# tach_key.net
KiCad netlist of a schematic drawn in Altium Designer
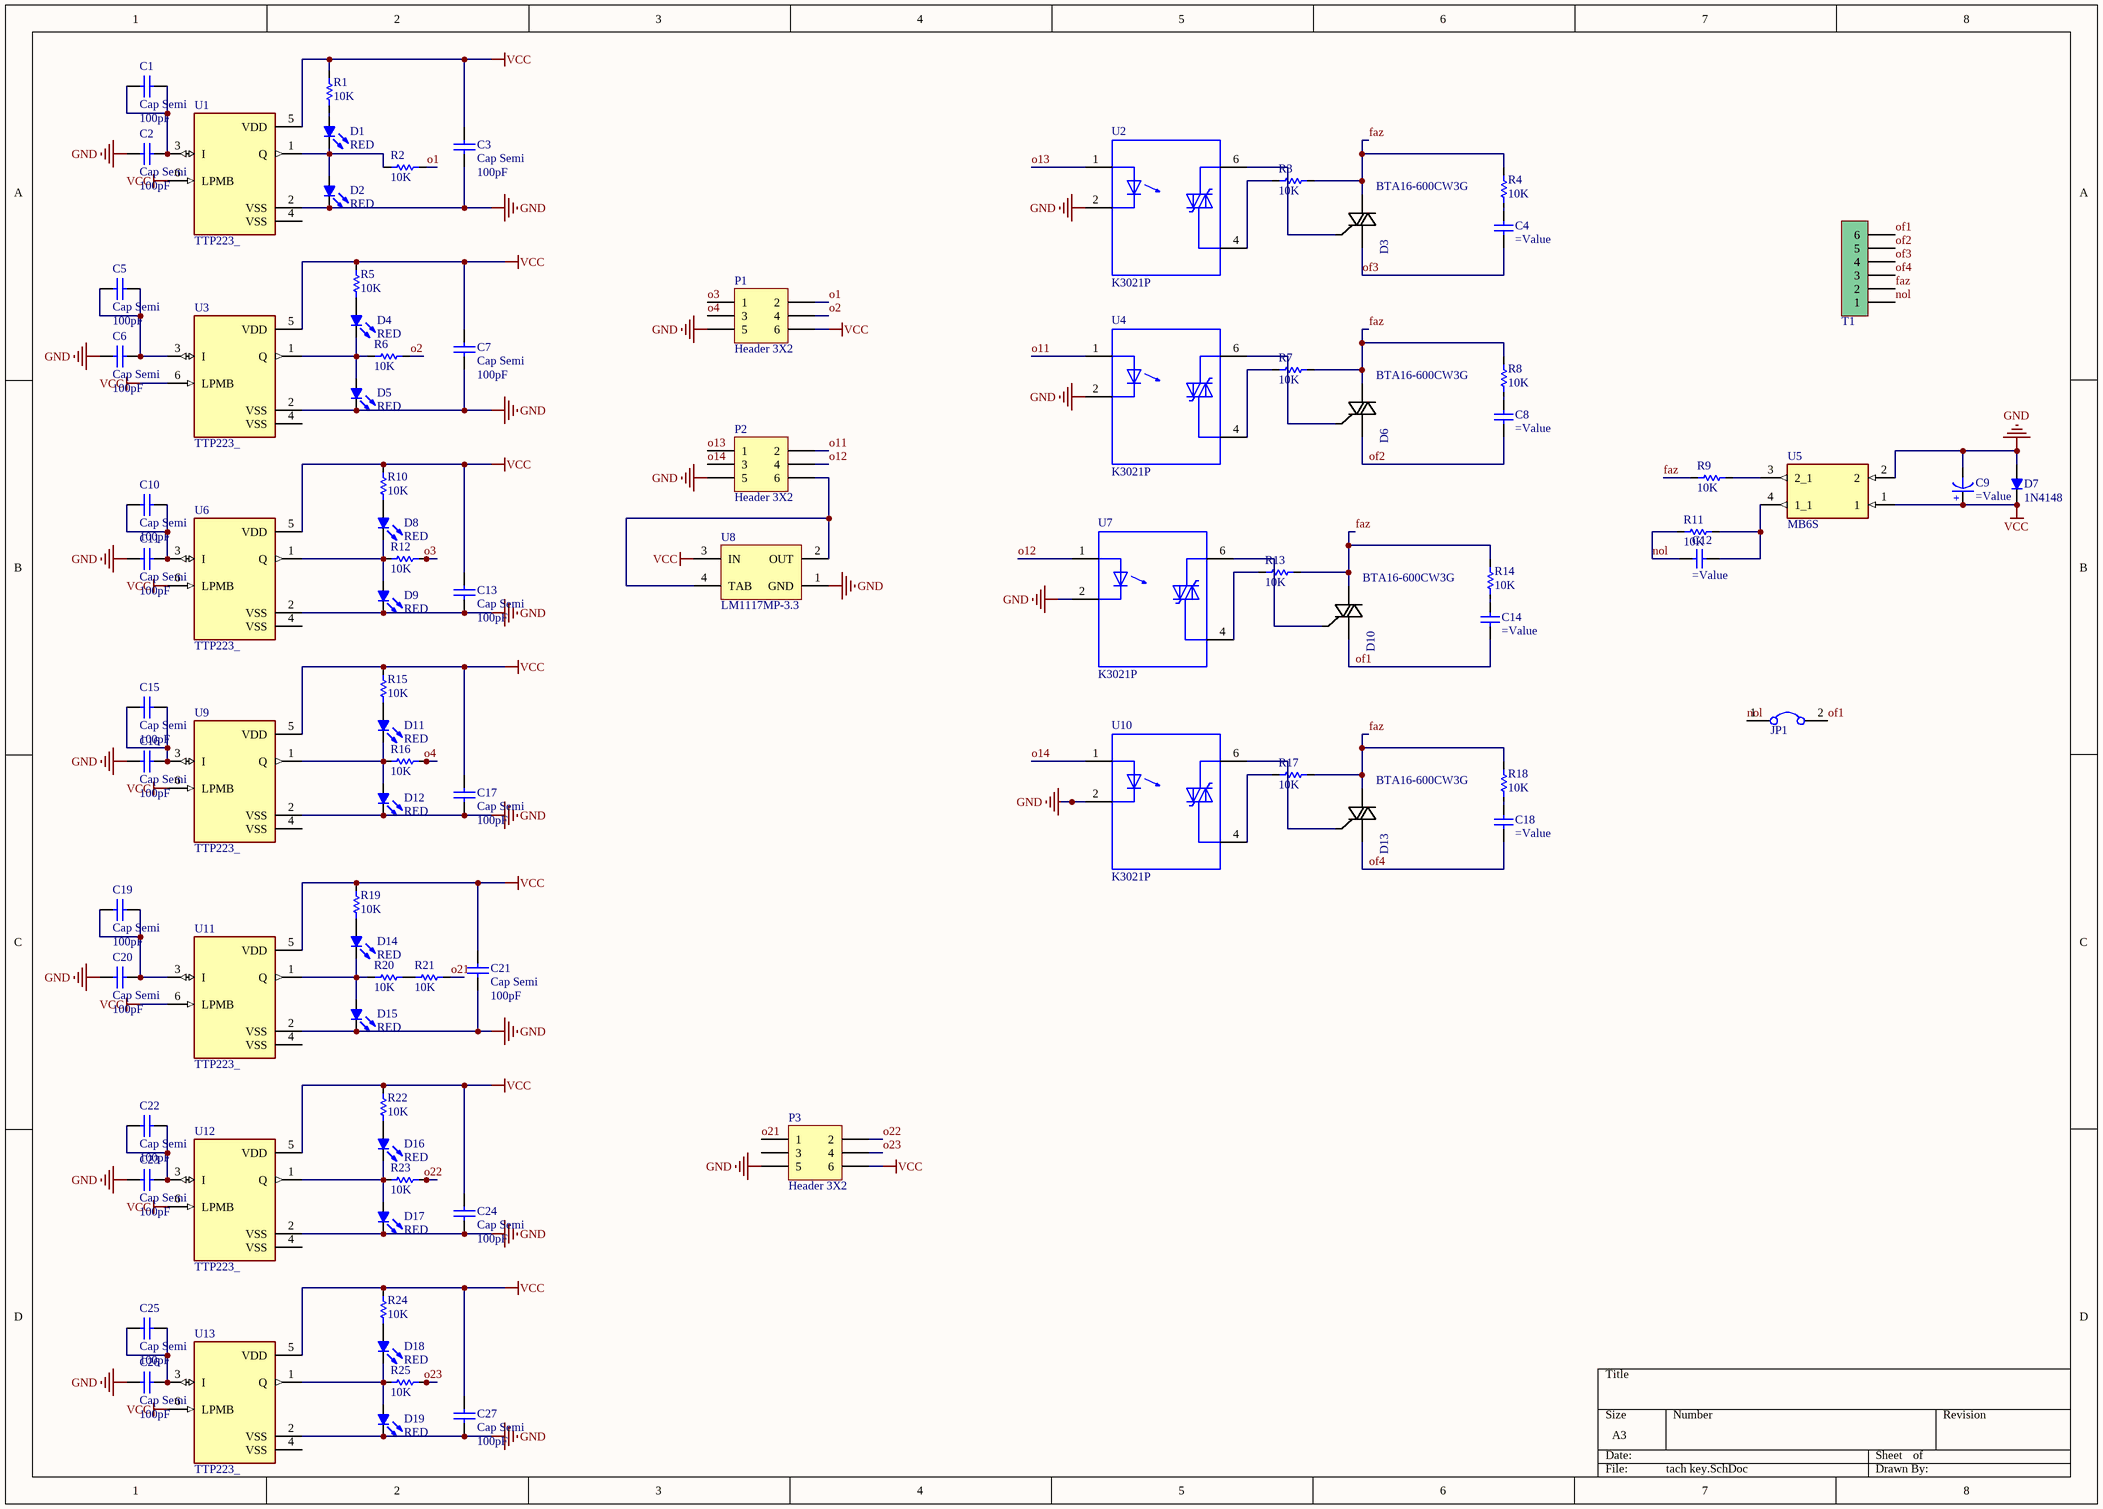
[diagram p0: tach key.SchDoc]

(export (version "E")
  (design (tool "Eeschema 10.0.6"))
  (components
    (comp (ref "C1")
      (value "Cap Semi")
      (footprint "C1206")
      (description "Capacitor (Semiconductor SIM Model)")
      (fields (field (name "ALTIUM_VALUE") "100pF") (field (name "PUBLISHER") "Altium Limited"))
      (libsource (lib "Miscellaneous Devices") (part "Cap Semi"))
    )
    (comp (ref "C2")
      (value "Cap Semi")
      (footprint "C1206")
      (description "Capacitor (Semiconductor SIM Model)")
      (fields (field (name "ALTIUM_VALUE") "100pF") (field (name "PUBLISHER") "Altium Limited"))
      (libsource (lib "Miscellaneous Devices") (part "Cap Semi"))
    )
    (comp (ref "C3")
      (value "Cap Semi")
      (footprint "C1206")
      (description "Capacitor (Semiconductor SIM Model)")
      (fields (field (name "ALTIUM_VALUE") "100pF") (field (name "PUBLISHER") "Altium Limited"))
      (libsource (lib "Miscellaneous Devices") (part "Cap Semi"))
    )
    (comp (ref "C4")
      (value "~")
      (footprint "CAP-30")
      (description "Capacitor")
      (libsource (lib "AltiumLib1") (part "Capacitor"))
    )
    (comp (ref "C5")
      (value "Cap Semi")
      (footprint "C1206")
      (description "Capacitor (Semiconductor SIM Model)")
      (fields (field (name "ALTIUM_VALUE") "100pF") (field (name "PUBLISHER") "Altium Limited"))
      (libsource (lib "Miscellaneous Devices") (part "Cap Semi"))
    )
    (comp (ref "C6")
      (value "Cap Semi")
      (footprint "C1206")
      (description "Capacitor (Semiconductor SIM Model)")
      (fields (field (name "ALTIUM_VALUE") "100pF") (field (name "PUBLISHER") "Altium Limited"))
      (libsource (lib "Miscellaneous Devices") (part "Cap Semi"))
    )
    (comp (ref "C7")
      (value "Cap Semi")
      (footprint "C1206")
      (description "Capacitor (Semiconductor SIM Model)")
      (fields (field (name "ALTIUM_VALUE") "100pF") (field (name "PUBLISHER") "Altium Limited"))
      (libsource (lib "Miscellaneous Devices") (part "Cap Semi"))
    )
    (comp (ref "C8")
      (value "~")
      (footprint "CAP-30")
      (description "Capacitor")
      (libsource (lib "AltiumLib1") (part "Capacitor"))
    )
    (comp (ref "C9")
      (value "~")
      (footprint "ELEC-CAP-RAD10-20")
      (description "Electrolytic Capacitor")
      (libsource (lib "AltiumLib1") (part "Capacitor Electrolytic"))
    )
    (comp (ref "C10")
      (value "Cap Semi")
      (footprint "C1206")
      (description "Capacitor (Semiconductor SIM Model)")
      (fields (field (name "ALTIUM_VALUE") "100pF") (field (name "PUBLISHER") "Altium Limited"))
      (libsource (lib "Miscellaneous Devices") (part "Cap Semi"))
    )
    (comp (ref "C11")
      (value "Cap Semi")
      (footprint "C1206")
      (description "Capacitor (Semiconductor SIM Model)")
      (fields (field (name "ALTIUM_VALUE") "100pF") (field (name "PUBLISHER") "Altium Limited"))
      (libsource (lib "Miscellaneous Devices") (part "Cap Semi"))
    )
    (comp (ref "C12")
      (value "~")
      (footprint "CAP-30")
      (description "Capacitor")
      (libsource (lib "AltiumLib1") (part "Capacitor"))
    )
    (comp (ref "C13")
      (value "Cap Semi")
      (footprint "C0805")
      (description "Capacitor (Semiconductor SIM Model)")
      (fields (field (name "ALTIUM_VALUE") "100pF") (field (name "PUBLISHER") "Altium Limited"))
      (libsource (lib "Miscellaneous Devices") (part "Cap Semi"))
    )
    (comp (ref "C14")
      (value "~")
      (footprint "CAP-30")
      (description "Capacitor")
      (libsource (lib "AltiumLib1") (part "Capacitor"))
    )
    (comp (ref "C15")
      (value "Cap Semi")
      (footprint "C1206")
      (description "Capacitor (Semiconductor SIM Model)")
      (fields (field (name "ALTIUM_VALUE") "100pF") (field (name "PUBLISHER") "Altium Limited"))
      (libsource (lib "Miscellaneous Devices") (part "Cap Semi"))
    )
    (comp (ref "C16")
      (value "Cap Semi")
      (footprint "C1206")
      (description "Capacitor (Semiconductor SIM Model)")
      (fields (field (name "ALTIUM_VALUE") "100pF") (field (name "PUBLISHER") "Altium Limited"))
      (libsource (lib "Miscellaneous Devices") (part "Cap Semi"))
    )
    (comp (ref "C17")
      (value "Cap Semi")
      (footprint "C0805")
      (description "Capacitor (Semiconductor SIM Model)")
      (fields (field (name "ALTIUM_VALUE") "100pF") (field (name "PUBLISHER") "Altium Limited"))
      (libsource (lib "Miscellaneous Devices") (part "Cap Semi"))
    )
    (comp (ref "C18")
      (value "~")
      (footprint "CAP-30")
      (description "Capacitor")
      (libsource (lib "AltiumLib1") (part "Capacitor"))
    )
    (comp (ref "C19")
      (value "Cap Semi")
      (footprint "C1206")
      (description "Capacitor (Semiconductor SIM Model)")
      (fields (field (name "ALTIUM_VALUE") "100pF") (field (name "PUBLISHER") "Altium Limited"))
      (libsource (lib "Miscellaneous Devices") (part "Cap Semi"))
    )
    (comp (ref "C20")
      (value "Cap Semi")
      (footprint "C1206")
      (description "Capacitor (Semiconductor SIM Model)")
      (fields (field (name "ALTIUM_VALUE") "100pF") (field (name "PUBLISHER") "Altium Limited"))
      (libsource (lib "Miscellaneous Devices") (part "Cap Semi"))
    )
    (comp (ref "C21")
      (value "Cap Semi")
      (footprint "C1206")
      (description "Capacitor (Semiconductor SIM Model)")
      (fields (field (name "ALTIUM_VALUE") "100pF") (field (name "PUBLISHER") "Altium Limited"))
      (libsource (lib "Miscellaneous Devices") (part "Cap Semi"))
    )
    (comp (ref "C22")
      (value "Cap Semi")
      (footprint "C1206")
      (description "Capacitor (Semiconductor SIM Model)")
      (fields (field (name "ALTIUM_VALUE") "100pF") (field (name "PUBLISHER") "Altium Limited"))
      (libsource (lib "Miscellaneous Devices") (part "Cap Semi"))
    )
    (comp (ref "C23")
      (value "Cap Semi")
      (footprint "C1206")
      (description "Capacitor (Semiconductor SIM Model)")
      (fields (field (name "ALTIUM_VALUE") "100pF") (field (name "PUBLISHER") "Altium Limited"))
      (libsource (lib "Miscellaneous Devices") (part "Cap Semi"))
    )
    (comp (ref "C24")
      (value "Cap Semi")
      (footprint "C0805")
      (description "Capacitor (Semiconductor SIM Model)")
      (fields (field (name "ALTIUM_VALUE") "100pF") (field (name "PUBLISHER") "Altium Limited"))
      (libsource (lib "Miscellaneous Devices") (part "Cap Semi"))
    )
    (comp (ref "C25")
      (value "Cap Semi")
      (footprint "C1206")
      (description "Capacitor (Semiconductor SIM Model)")
      (fields (field (name "ALTIUM_VALUE") "100pF") (field (name "PUBLISHER") "Altium Limited"))
      (libsource (lib "Miscellaneous Devices") (part "Cap Semi"))
    )
    (comp (ref "C26")
      (value "Cap Semi")
      (footprint "C1206")
      (description "Capacitor (Semiconductor SIM Model)")
      (fields (field (name "ALTIUM_VALUE") "100pF") (field (name "PUBLISHER") "Altium Limited"))
      (libsource (lib "Miscellaneous Devices") (part "Cap Semi"))
    )
    (comp (ref "C27")
      (value "Cap Semi")
      (footprint "C0805")
      (description "Capacitor (Semiconductor SIM Model)")
      (fields (field (name "ALTIUM_VALUE") "100pF") (field (name "PUBLISHER") "Altium Limited"))
      (libsource (lib "Miscellaneous Devices") (part "Cap Semi"))
    )
    (comp (ref "D1")
      (value "MODEL")
      (footprint "RES 0805 (2012X06L)")
      (description "Typical LED")
      (fields (field (name "COLOR") "RED"))
      (libsource (lib "AltiumLib1") (part "LED 5mm"))
    )
    (comp (ref "D2")
      (value "MODEL")
      (footprint "RES 0805 (2012X06L)")
      (description "Typical LED")
      (fields (field (name "COLOR") "RED"))
      (libsource (lib "AltiumLib1") (part "LED 5mm"))
    )
    (comp (ref "D3")
      (value "BTA16-600CW3G")
      (footprint "*TO254P1028X482X1968-3")
      (description "TRIAC Standard 600V 16A Through Hole TO-220AB")
      (fields (field (name "MF") "Littelfuse Inc."))
      (libsource (lib "BTA16-600CW3G") (part "BTA16-600CW3G"))
    )
    (comp (ref "D4")
      (value "MODEL")
      (footprint "RES 0805 (2012X06L)")
      (description "Typical LED")
      (fields (field (name "COLOR") "RED"))
      (libsource (lib "AltiumLib1") (part "LED 5mm"))
    )
    (comp (ref "D5")
      (value "MODEL")
      (footprint "RES 0805 (2012X06L)")
      (description "Typical LED")
      (fields (field (name "COLOR") "RED"))
      (libsource (lib "AltiumLib1") (part "LED 5mm"))
    )
    (comp (ref "D6")
      (value "BTA16-600CW3G")
      (footprint "*TO254P1028X482X1968-3")
      (description "TRIAC Standard 600V 16A Through Hole TO-220AB")
      (fields (field (name "MF") "Littelfuse Inc."))
      (libsource (lib "BTA16-600CW3G") (part "BTA16-600CW3G"))
    )
    (comp (ref "D7")
      (value "MODEL")
      (footprint "DO-35-STAND")
      (description "Diode")
      (fields (field (name "MODEL") "1N4148"))
      (libsource (lib "AltiumLib1") (part "Diode"))
    )
    (comp (ref "D8")
      (value "MODEL")
      (footprint "RES 0805 (2012X06L)")
      (description "Typical LED")
      (fields (field (name "COLOR") "RED"))
      (libsource (lib "AltiumLib1") (part "LED 5mm"))
    )
    (comp (ref "D9")
      (value "MODEL")
      (footprint "RES 0805 (2012X06L)")
      (description "Typical LED")
      (fields (field (name "COLOR") "RED"))
      (libsource (lib "AltiumLib1") (part "LED 5mm"))
    )
    (comp (ref "D10")
      (value "BTA16-600CW3G")
      (footprint "*TO254P1028X482X1968-3")
      (description "TRIAC Standard 600V 16A Through Hole TO-220AB")
      (fields (field (name "MF") "Littelfuse Inc."))
      (libsource (lib "BTA16-600CW3G") (part "BTA16-600CW3G"))
    )
    (comp (ref "D11")
      (value "MODEL")
      (footprint "RES 0805 (2012X06L)")
      (description "Typical LED")
      (fields (field (name "COLOR") "RED"))
      (libsource (lib "AltiumLib1") (part "LED 5mm"))
    )
    (comp (ref "D12")
      (value "MODEL")
      (footprint "RES 0805 (2012X06L)")
      (description "Typical LED")
      (fields (field (name "COLOR") "RED"))
      (libsource (lib "AltiumLib1") (part "LED 5mm"))
    )
    (comp (ref "D13")
      (value "BTA16-600CW3G")
      (footprint "*TO254P1028X482X1968-3")
      (description "TRIAC Standard 600V 16A Through Hole TO-220AB")
      (fields (field (name "MF") "Littelfuse Inc."))
      (libsource (lib "BTA16-600CW3G") (part "BTA16-600CW3G"))
    )
    (comp (ref "D14")
      (value "MODEL")
      (footprint "RES 0805 (2012X06L)")
      (description "Typical LED")
      (fields (field (name "COLOR") "RED"))
      (libsource (lib "AltiumLib1") (part "LED 5mm"))
    )
    (comp (ref "D15")
      (value "MODEL")
      (footprint "RES 0805 (2012X06L)")
      (description "Typical LED")
      (fields (field (name "COLOR") "RED"))
      (libsource (lib "AltiumLib1") (part "LED 5mm"))
    )
    (comp (ref "D16")
      (value "MODEL")
      (footprint "RES 0805 (2012X06L)")
      (description "Typical LED")
      (fields (field (name "COLOR") "RED"))
      (libsource (lib "AltiumLib1") (part "LED 5mm"))
    )
    (comp (ref "D17")
      (value "MODEL")
      (footprint "RES 0805 (2012X06L)")
      (description "Typical LED")
      (fields (field (name "COLOR") "RED"))
      (libsource (lib "AltiumLib1") (part "LED 5mm"))
    )
    (comp (ref "D18")
      (value "MODEL")
      (footprint "RES 0805 (2012X06L)")
      (description "Typical LED")
      (fields (field (name "COLOR") "RED"))
      (libsource (lib "AltiumLib1") (part "LED 5mm"))
    )
    (comp (ref "D19")
      (value "MODEL")
      (footprint "RES 0805 (2012X06L)")
      (description "Typical LED")
      (fields (field (name "COLOR") "RED"))
      (libsource (lib "AltiumLib1") (part "LED 5mm"))
    )
    (comp (ref "JP1")
      (value "Jumper")
      (footprint "Header 2X1")
      (libsource (lib "AltiumLib1") (part "Jumper"))
    )
    (comp (ref "P1")
      (value "Header 3X2")
      (footprint "HDR2X3")
      (description "Header, 3-Pin, Dual row")
      (fields (field (name "PUBLISHER") "Altium Limited"))
      (libsource (lib "Miscellaneous Connectors") (part "Header 3X2"))
    )
    (comp (ref "P2")
      (value "Header 3X2")
      (footprint "MHDR2X3")
      (description "Header, 3-Pin, Dual row")
      (fields (field (name "PUBLISHER") "Altium Limited"))
      (libsource (lib "Miscellaneous Connectors") (part "Header 3X2"))
    )
    (comp (ref "P3")
      (value "Header 3X2")
      (footprint "MHDR2X3")
      (description "Header, 3-Pin, Dual row")
      (fields (field (name "PUBLISHER") "Altium Limited"))
      (libsource (lib "Miscellaneous Connectors") (part "Header 3X2"))
    )
    (comp (ref "R1")
      (value "10K")
      (footprint "RES 1206 (3216X08L)")
      (description "Resistor")
      (fields (field (name "TOLERANCE") "5%") (field (name "POWER") "1/4 W"))
      (libsource (lib "AltiumLib1") (part "Resistor"))
    )
    (comp (ref "R2")
      (value "10K")
      (footprint "RES 1206 (3216X08L)")
      (description "Resistor")
      (fields (field (name "TOLERANCE") "5%") (field (name "POWER") "1/4 W"))
      (libsource (lib "AltiumLib1") (part "Resistor"))
    )
    (comp (ref "R3")
      (value "10K")
      (footprint "RES 1206 (3216X08L)")
      (description "Resistor")
      (fields (field (name "TOLERANCE") "5%") (field (name "POWER") "1/4 W"))
      (libsource (lib "AltiumLib1") (part "Resistor"))
    )
    (comp (ref "R4")
      (value "10K")
      (footprint "RES 1206 (3216X08L)")
      (description "Resistor")
      (fields (field (name "TOLERANCE") "5%") (field (name "POWER") "1/4 W"))
      (libsource (lib "AltiumLib1") (part "Resistor"))
    )
    (comp (ref "R5")
      (value "10K")
      (footprint "RES 1206 (3216X08L)")
      (description "Resistor")
      (fields (field (name "TOLERANCE") "5%") (field (name "POWER") "1/4 W"))
      (libsource (lib "AltiumLib1") (part "Resistor"))
    )
    (comp (ref "R6")
      (value "10K")
      (footprint "RES 1206 (3216X08L)")
      (description "Resistor")
      (fields (field (name "TOLERANCE") "5%") (field (name "POWER") "1/4 W"))
      (libsource (lib "AltiumLib1") (part "Resistor"))
    )
    (comp (ref "R7")
      (value "10K")
      (footprint "RES 1206 (3216X08L)")
      (description "Resistor")
      (fields (field (name "TOLERANCE") "5%") (field (name "POWER") "1/4 W"))
      (libsource (lib "AltiumLib1") (part "Resistor"))
    )
    (comp (ref "R8")
      (value "10K")
      (footprint "RES 1206 (3216X08L)")
      (description "Resistor")
      (fields (field (name "TOLERANCE") "5%") (field (name "POWER") "1/4 W"))
      (libsource (lib "AltiumLib1") (part "Resistor"))
    )
    (comp (ref "R9")
      (value "10K")
      (footprint "Res-(2/1)")
      (description "Resistor")
      (fields (field (name "TOLERANCE") "5%") (field (name "POWER") "1/4 W"))
      (libsource (lib "AltiumLib1") (part "Resistor"))
    )
    (comp (ref "R10")
      (value "10K")
      (footprint "RES 1206 (3216X08L)")
      (description "Resistor")
      (fields (field (name "TOLERANCE") "5%") (field (name "POWER") "1/4 W"))
      (libsource (lib "AltiumLib1") (part "Resistor"))
    )
    (comp (ref "R11")
      (value "10K")
      (footprint "Res-(1/4)")
      (description "Resistor")
      (fields (field (name "TOLERANCE") "5%") (field (name "POWER") "1/4 W"))
      (libsource (lib "AltiumLib1") (part "Resistor"))
    )
    (comp (ref "R12")
      (value "10K")
      (footprint "RES 1206 (3216X08L)")
      (description "Resistor")
      (fields (field (name "TOLERANCE") "5%") (field (name "POWER") "1/4 W"))
      (libsource (lib "AltiumLib1") (part "Resistor"))
    )
    (comp (ref "R13")
      (value "10K")
      (footprint "RES 1206 (3216X08L)")
      (description "Resistor")
      (fields (field (name "TOLERANCE") "5%") (field (name "POWER") "1/4 W"))
      (libsource (lib "AltiumLib1") (part "Resistor"))
    )
    (comp (ref "R14")
      (value "10K")
      (footprint "RES 1206 (3216X08L)")
      (description "Resistor")
      (fields (field (name "TOLERANCE") "5%") (field (name "POWER") "1/4 W"))
      (libsource (lib "AltiumLib1") (part "Resistor"))
    )
    (comp (ref "R15")
      (value "10K")
      (footprint "RES 1206 (3216X08L)")
      (description "Resistor")
      (fields (field (name "TOLERANCE") "5%") (field (name "POWER") "1/4 W"))
      (libsource (lib "AltiumLib1") (part "Resistor"))
    )
    (comp (ref "R16")
      (value "10K")
      (footprint "RES 1206 (3216X08L)")
      (description "Resistor")
      (fields (field (name "TOLERANCE") "5%") (field (name "POWER") "1/4 W"))
      (libsource (lib "AltiumLib1") (part "Resistor"))
    )
    (comp (ref "R17")
      (value "10K")
      (footprint "RES 1206 (3216X08L)")
      (description "Resistor")
      (fields (field (name "TOLERANCE") "5%") (field (name "POWER") "1/4 W"))
      (libsource (lib "AltiumLib1") (part "Resistor"))
    )
    (comp (ref "R18")
      (value "10K")
      (footprint "RES 1206 (3216X08L)")
      (description "Resistor")
      (fields (field (name "TOLERANCE") "5%") (field (name "POWER") "1/4 W"))
      (libsource (lib "AltiumLib1") (part "Resistor"))
    )
    (comp (ref "R19")
      (value "10K")
      (footprint "RES 1206 (3216X08L)")
      (description "Resistor")
      (fields (field (name "TOLERANCE") "5%") (field (name "POWER") "1/4 W"))
      (libsource (lib "AltiumLib1") (part "Resistor"))
    )
    (comp (ref "R20")
      (value "10K")
      (footprint "RES 1206 (3216X08L)")
      (description "Resistor")
      (fields (field (name "TOLERANCE") "5%") (field (name "POWER") "1/4 W"))
      (libsource (lib "AltiumLib1") (part "Resistor"))
    )
    (comp (ref "R21")
      (value "10K")
      (footprint "RES 1206 (3216X08L)")
      (description "Resistor")
      (fields (field (name "TOLERANCE") "5%") (field (name "POWER") "1/4 W"))
      (libsource (lib "AltiumLib1") (part "Resistor"))
    )
    (comp (ref "R22")
      (value "10K")
      (footprint "RES 1206 (3216X08L)")
      (description "Resistor")
      (fields (field (name "TOLERANCE") "5%") (field (name "POWER") "1/4 W"))
      (libsource (lib "AltiumLib1") (part "Resistor"))
    )
    (comp (ref "R23")
      (value "10K")
      (footprint "RES 1206 (3216X08L)")
      (description "Resistor")
      (fields (field (name "TOLERANCE") "5%") (field (name "POWER") "1/4 W"))
      (libsource (lib "AltiumLib1") (part "Resistor"))
    )
    (comp (ref "R24")
      (value "10K")
      (footprint "RES 1206 (3216X08L)")
      (description "Resistor")
      (fields (field (name "TOLERANCE") "5%") (field (name "POWER") "1/4 W"))
      (libsource (lib "AltiumLib1") (part "Resistor"))
    )
    (comp (ref "R25")
      (value "10K")
      (footprint "RES 1206 (3216X08L)")
      (description "Resistor")
      (fields (field (name "TOLERANCE") "5%") (field (name "POWER") "1/4 W"))
      (libsource (lib "AltiumLib1") (part "Resistor"))
    )
    (comp (ref "T1")
      (value "Phoenix terminal")
      (footprint "phoenix terminal 6")
      (description "Terminal 6 Pin")
      (fields (field (name "DESIGNER") "Seyed Mohsen Ghasemain") (field (name "E-MAIL") "picpars@gmail.com"))
      (libsource (lib "PicPars.com_usefully_Library") (part "Phoenix terminal 6"))
    )
    (comp (ref "U1")
      (value "TTP223_")
      (footprint "SOT95P285X126-6N")
      (fields (field (name "MP") "TTP223") (field (name "MF") "KOA Speer"))
      (libsource (lib "TTP223_") (part "TTP223_"))
    )
    (comp (ref "U2")
      (value "K3021P")
      (footprint "DIP762W50P254L730H410Q6")
      (description "Optoisolator Triac Output 5300Vrms 1 Channel 6-DIP")
      (fields (field (name "MF") "Vishay Semiconductor"))
      (libsource (lib "K3021P") (part "K3021P"))
    )
    (comp (ref "U3")
      (value "TTP223_")
      (footprint "SOT95P285X126-6N")
      (fields (field (name "MP") "TTP223") (field (name "MF") "KOA Speer"))
      (libsource (lib "TTP223_") (part "TTP223_"))
    )
    (comp (ref "U4")
      (value "K3021P")
      (footprint "DIP762W50P254L730H410Q6")
      (description "Optoisolator Triac Output 5300Vrms 1 Channel 6-DIP")
      (fields (field (name "MF") "Vishay Semiconductor"))
      (libsource (lib "K3021P") (part "K3021P"))
    )
    (comp (ref "U5")
      (value "MB6S")
      (footprint "SOIC245P670X270-4N")
      (description "Bridge Rectifier Single Phase Standard 600V Surface Mount 4-SOIC")
      (fields (field (name "MF") "ON Semiconductor") (field (name "DIGI-KEY_PART_NUMBER") "MB6SCT-ND"))
      (libsource (lib "MB6S") (part "MB6S"))
    )
    (comp (ref "U6")
      (value "TTP223_")
      (footprint "SOT95P285X126-6N")
      (fields (field (name "MP") "TTP223") (field (name "MF") "KOA Speer"))
      (libsource (lib "TTP223_") (part "TTP223_"))
    )
    (comp (ref "U7")
      (value "K3021P")
      (footprint "DIP762W50P254L730H410Q6")
      (description "Optoisolator Triac Output 5300Vrms 1 Channel 6-DIP")
      (fields (field (name "MF") "Vishay Semiconductor"))
      (libsource (lib "K3021P") (part "K3021P"))
    )
    (comp (ref "U8")
      (value "LM1117MP-3.3")
      (footprint "MP04A_N")
      (description "800mA Low-Dropout Linear Regulator")
      (fields
        (field (name "MANUFACTURER") "National Semiconductor")
        (field (name "DIGIKEYPARTNUMBER") "LM1117MP-3.3CT-ND")
        (field (name "PUBLISHER") "Altium Limited")
      )
      (libsource (lib "NSC LDO") (part "LM1117MP-3.3"))
    )
    (comp (ref "U9")
      (value "TTP223_")
      (footprint "SOT95P285X126-6N")
      (fields (field (name "MP") "TTP223") (field (name "MF") "KOA Speer"))
      (libsource (lib "TTP223_") (part "TTP223_"))
    )
    (comp (ref "U10")
      (value "K3021P")
      (footprint "DIP762W50P254L730H410Q6")
      (description "Optoisolator Triac Output 5300Vrms 1 Channel 6-DIP")
      (fields (field (name "MF") "Vishay Semiconductor"))
      (libsource (lib "K3021P") (part "K3021P"))
    )
    (comp (ref "U11")
      (value "TTP223_")
      (footprint "SOT95P285X126-6N")
      (fields (field (name "MP") "TTP223") (field (name "MF") "KOA Speer"))
      (libsource (lib "TTP223_") (part "TTP223_"))
    )
    (comp (ref "U12")
      (value "TTP223_")
      (footprint "SOT95P285X126-6N")
      (fields (field (name "MP") "TTP223") (field (name "MF") "KOA Speer"))
      (libsource (lib "TTP223_") (part "TTP223_"))
    )
    (comp (ref "U13")
      (value "TTP223_")
      (footprint "SOT95P285X126-6N")
      (fields (field (name "MP") "TTP223") (field (name "MF") "KOA Speer"))
      (libsource (lib "TTP223_") (part "TTP223_"))
    )
  )
  (nets
    (net (code "1") (name "/faz") (class "Default")
      (node (ref "D10") (pin "2") (pinfunction "MT2_2") (pintype "passive"))
      (node (ref "D13") (pin "2") (pinfunction "MT2_2") (pintype "passive"))
      (node (ref "D3") (pin "2") (pinfunction "MT2_2") (pintype "passive"))
      (node (ref "D6") (pin "2") (pinfunction "MT2_2") (pintype "passive"))
      (node (ref "R13") (pin "2") (pinfunction "2_2") (pintype "passive"))
      (node (ref "R14") (pin "2") (pinfunction "2_2") (pintype "passive"))
      (node (ref "R17") (pin "2") (pinfunction "2_2") (pintype "passive"))
      (node (ref "R18") (pin "2") (pinfunction "2_2") (pintype "passive"))
      (node (ref "R3") (pin "2") (pinfunction "2_2") (pintype "passive"))
      (node (ref "R4") (pin "2") (pinfunction "2_2") (pintype "passive"))
      (node (ref "R7") (pin "2") (pinfunction "2_2") (pintype "passive"))
      (node (ref "R8") (pin "2") (pinfunction "2_2") (pintype "passive"))
      (node (ref "R9") (pin "2") (pinfunction "2_2") (pintype "passive"))
      (node (ref "T1") (pin "2") (pinfunction "2_2") (pintype "passive"))
    )
    (net (code "2") (name "/nol") (class "Default")
      (node (ref "C12") (pin "1") (pinfunction "+_1") (pintype "passive"))
      (node (ref "JP1") (pin "1") (pinfunction "1_1") (pintype "passive"))
      (node (ref "R11") (pin "2") (pinfunction "2_2") (pintype "passive"))
      (node (ref "T1") (pin "1") (pinfunction "1_1") (pintype "passive"))
    )
    (net (code "3") (name "/o1") (class "Default")
      (node (ref "P1") (pin "2") (pinfunction "2_2") (pintype "passive"))
      (node (ref "R2") (pin "2") (pinfunction "2_2") (pintype "passive"))
    )
    (net (code "4") (name "/o2") (class "Default")
      (node (ref "P1") (pin "4") (pinfunction "4_4") (pintype "passive"))
      (node (ref "R6") (pin "2") (pinfunction "2_2") (pintype "passive"))
    )
    (net (code "5") (name "/o3") (class "Default")
      (node (ref "P1") (pin "1") (pinfunction "1_1") (pintype "passive"))
      (node (ref "R12") (pin "2") (pinfunction "2_2") (pintype "passive"))
    )
    (net (code "6") (name "/o4") (class "Default")
      (node (ref "P1") (pin "3") (pinfunction "3_3") (pintype "passive"))
      (node (ref "R16") (pin "2") (pinfunction "2_2") (pintype "passive"))
    )
    (net (code "7") (name "/o11") (class "Default")
      (node (ref "P2") (pin "2") (pinfunction "2_2") (pintype "passive"))
      (node (ref "U4") (pin "1") (pinfunction "A_1") (pintype "passive"))
    )
    (net (code "8") (name "/o12") (class "Default")
      (node (ref "P2") (pin "4") (pinfunction "4_4") (pintype "passive"))
      (node (ref "U7") (pin "1") (pinfunction "A_1") (pintype "passive"))
    )
    (net (code "9") (name "/o13") (class "Default")
      (node (ref "P2") (pin "1") (pinfunction "1_1") (pintype "passive"))
      (node (ref "U2") (pin "1") (pinfunction "A_1") (pintype "passive"))
    )
    (net (code "10") (name "/o14") (class "Default")
      (node (ref "P2") (pin "3") (pinfunction "3_3") (pintype "passive"))
      (node (ref "U10") (pin "1") (pinfunction "A_1") (pintype "passive"))
    )
    (net (code "11") (name "/o21") (class "Default")
      (node (ref "P3") (pin "1") (pinfunction "1_1") (pintype "passive"))
      (node (ref "R21") (pin "2") (pinfunction "2_2") (pintype "passive"))
    )
    (net (code "12") (name "/o22") (class "Default")
      (node (ref "P3") (pin "2") (pinfunction "2_2") (pintype "passive"))
      (node (ref "R23") (pin "2") (pinfunction "2_2") (pintype "passive"))
    )
    (net (code "13") (name "/o23") (class "Default")
      (node (ref "P3") (pin "4") (pinfunction "4_4") (pintype "passive"))
      (node (ref "R25") (pin "2") (pinfunction "2_2") (pintype "passive"))
    )
    (net (code "14") (name "/of1") (class "Default")
      (node (ref "C14") (pin "1") (pinfunction "+_1") (pintype "passive"))
      (node (ref "D10") (pin "1") (pinfunction "MT1_1") (pintype "passive"))
      (node (ref "JP1") (pin "2") (pinfunction "2_2") (pintype "passive"))
      (node (ref "T1") (pin "6") (pinfunction "6_6") (pintype "passive"))
    )
    (net (code "15") (name "/of2") (class "Default")
      (node (ref "C8") (pin "1") (pinfunction "+_1") (pintype "passive"))
      (node (ref "D6") (pin "1") (pinfunction "MT1_1") (pintype "passive"))
      (node (ref "T1") (pin "5") (pinfunction "5_5") (pintype "passive"))
    )
    (net (code "16") (name "/of3") (class "Default")
      (node (ref "C4") (pin "1") (pinfunction "+_1") (pintype "passive"))
      (node (ref "D3") (pin "1") (pinfunction "MT1_1") (pintype "passive"))
      (node (ref "T1") (pin "4") (pinfunction "4_4") (pintype "passive"))
    )
    (net (code "17") (name "/of4") (class "Default")
      (node (ref "C18") (pin "1") (pinfunction "+_1") (pintype "passive"))
      (node (ref "D13") (pin "1") (pinfunction "MT1_1") (pintype "passive"))
      (node (ref "T1") (pin "3") (pinfunction "3_3") (pintype "passive"))
    )
    (net (code "18") (name "GND") (class "Default")
      (node (ref "C11") (pin "2") (pinfunction "2_2") (pintype "passive"))
      (node (ref "C13") (pin "1") (pinfunction "1_1") (pintype "passive"))
      (node (ref "C16") (pin "2") (pinfunction "2_2") (pintype "passive"))
      (node (ref "C17") (pin "1") (pinfunction "1_1") (pintype "passive"))
      (node (ref "C2") (pin "2") (pinfunction "2_2") (pintype "passive"))
      (node (ref "C20") (pin "2") (pinfunction "2_2") (pintype "passive"))
      (node (ref "C21") (pin "1") (pinfunction "1_1") (pintype "passive"))
      (node (ref "C23") (pin "2") (pinfunction "2_2") (pintype "passive"))
      (node (ref "C24") (pin "1") (pinfunction "1_1") (pintype "passive"))
      (node (ref "C26") (pin "2") (pinfunction "2_2") (pintype "passive"))
      (node (ref "C27") (pin "1") (pinfunction "1_1") (pintype "passive"))
      (node (ref "C3") (pin "1") (pinfunction "1_1") (pintype "passive"))
      (node (ref "C6") (pin "2") (pinfunction "2_2") (pintype "passive"))
      (node (ref "C7") (pin "1") (pinfunction "1_1") (pintype "passive"))
      (node (ref "C9") (pin "1") (pinfunction "-_1") (pintype "passive"))
      (node (ref "D12") (pin "2") (pinfunction "K_2") (pintype "passive"))
      (node (ref "D15") (pin "2") (pinfunction "K_2") (pintype "passive"))
      (node (ref "D17") (pin "2") (pinfunction "K_2") (pintype "passive"))
      (node (ref "D19") (pin "2") (pinfunction "K_2") (pintype "passive"))
      (node (ref "D2") (pin "2") (pinfunction "K_2") (pintype "passive"))
      (node (ref "D5") (pin "2") (pinfunction "K_2") (pintype "passive"))
      (node (ref "D7") (pin "1") (pinfunction "A_1") (pintype "passive"))
      (node (ref "D9") (pin "2") (pinfunction "K_2") (pintype "passive"))
      (node (ref "P1") (pin "5") (pinfunction "5_5") (pintype "passive"))
      (node (ref "P2") (pin "5") (pinfunction "5_5") (pintype "passive"))
      (node (ref "P3") (pin "5") (pinfunction "5_5") (pintype "passive"))
      (node (ref "U1") (pin "2") (pinfunction "VSS_2") (pintype "power_in"))
      (node (ref "U10") (pin "2") (pinfunction "C_2") (pintype "passive"))
      (node (ref "U11") (pin "2") (pinfunction "VSS_2") (pintype "power_in"))
      (node (ref "U12") (pin "2") (pinfunction "VSS_2") (pintype "power_in"))
      (node (ref "U13") (pin "2") (pinfunction "VSS_2") (pintype "power_in"))
      (node (ref "U2") (pin "2") (pinfunction "C_2") (pintype "passive"))
      (node (ref "U3") (pin "2") (pinfunction "VSS_2") (pintype "power_in"))
      (node (ref "U4") (pin "2") (pinfunction "C_2") (pintype "passive"))
      (node (ref "U5") (pin "2") (pinfunction "2_2") (pintype "input"))
      (node (ref "U6") (pin "2") (pinfunction "VSS_2") (pintype "power_in"))
      (node (ref "U7") (pin "2") (pinfunction "C_2") (pintype "passive"))
      (node (ref "U8") (pin "1") (pinfunction "GND_1") (pintype "power_in"))
      (node (ref "U9") (pin "2") (pinfunction "VSS_2") (pintype "power_in"))
    )
    (net (code "19") (name "Net-(C4--)") (class "Default")
      (node (ref "C4") (pin "2") (pinfunction "-_2") (pintype "passive"))
      (node (ref "R4") (pin "1") (pinfunction "1_1") (pintype "passive"))
    )
    (net (code "20") (name "Net-(C8--)") (class "Default")
      (node (ref "C8") (pin "2") (pinfunction "-_2") (pintype "passive"))
      (node (ref "R8") (pin "1") (pinfunction "1_1") (pintype "passive"))
    )
    (net (code "21") (name "Net-(C12--)") (class "Default")
      (node (ref "C12") (pin "2") (pinfunction "-_2") (pintype "passive"))
      (node (ref "R11") (pin "1") (pinfunction "1_1") (pintype "passive"))
      (node (ref "U5") (pin "4") (pinfunction "1_1_4") (pintype "output"))
    )
    (net (code "22") (name "Net-(C14--)") (class "Default")
      (node (ref "C14") (pin "2") (pinfunction "-_2") (pintype "passive"))
      (node (ref "R14") (pin "1") (pinfunction "1_1") (pintype "passive"))
    )
    (net (code "23") (name "Net-(C18--)") (class "Default")
      (node (ref "C18") (pin "2") (pinfunction "-_2") (pintype "passive"))
      (node (ref "R18") (pin "1") (pinfunction "1_1") (pintype "passive"))
    )
    (net (code "24") (name "Net-(D1-A)") (class "Default")
      (node (ref "D1") (pin "1") (pinfunction "A_1") (pintype "passive"))
      (node (ref "R1") (pin "1") (pinfunction "1_1") (pintype "passive"))
    )
    (net (code "25") (name "Net-(D1-K)") (class "Default")
      (node (ref "D1") (pin "2") (pinfunction "K_2") (pintype "passive"))
      (node (ref "D2") (pin "1") (pinfunction "A_1") (pintype "passive"))
      (node (ref "R2") (pin "1") (pinfunction "1_1") (pintype "passive"))
      (node (ref "U1") (pin "1") (pinfunction "Q_1") (pintype "output"))
    )
    (net (code "26") (name "Net-(D3-G)") (class "Default")
      (node (ref "D3") (pin "3") (pinfunction "G_3") (pintype "passive"))
      (node (ref "U2") (pin "6") (pinfunction "MT2_6") (pintype "passive"))
    )
    (net (code "27") (name "Net-(D4-A)") (class "Default")
      (node (ref "D4") (pin "1") (pinfunction "A_1") (pintype "passive"))
      (node (ref "R5") (pin "1") (pinfunction "1_1") (pintype "passive"))
    )
    (net (code "28") (name "Net-(D4-K)") (class "Default")
      (node (ref "D4") (pin "2") (pinfunction "K_2") (pintype "passive"))
      (node (ref "D5") (pin "1") (pinfunction "A_1") (pintype "passive"))
      (node (ref "R6") (pin "1") (pinfunction "1_1") (pintype "passive"))
      (node (ref "U3") (pin "1") (pinfunction "Q_1") (pintype "output"))
    )
    (net (code "29") (name "Net-(D6-G)") (class "Default")
      (node (ref "D6") (pin "3") (pinfunction "G_3") (pintype "passive"))
      (node (ref "U4") (pin "6") (pinfunction "MT2_6") (pintype "passive"))
    )
    (net (code "30") (name "Net-(D8-A)") (class "Default")
      (node (ref "D8") (pin "1") (pinfunction "A_1") (pintype "passive"))
      (node (ref "R10") (pin "1") (pinfunction "1_1") (pintype "passive"))
    )
    (net (code "31") (name "Net-(D8-K)") (class "Default")
      (node (ref "D8") (pin "2") (pinfunction "K_2") (pintype "passive"))
      (node (ref "D9") (pin "1") (pinfunction "A_1") (pintype "passive"))
      (node (ref "R12") (pin "1") (pinfunction "1_1") (pintype "passive"))
      (node (ref "U6") (pin "1") (pinfunction "Q_1") (pintype "output"))
    )
    (net (code "32") (name "Net-(D10-G)") (class "Default")
      (node (ref "D10") (pin "3") (pinfunction "G_3") (pintype "passive"))
      (node (ref "U7") (pin "6") (pinfunction "MT2_6") (pintype "passive"))
    )
    (net (code "33") (name "Net-(D11-A)") (class "Default")
      (node (ref "D11") (pin "1") (pinfunction "A_1") (pintype "passive"))
      (node (ref "R15") (pin "1") (pinfunction "1_1") (pintype "passive"))
    )
    (net (code "34") (name "Net-(D11-K)") (class "Default")
      (node (ref "D11") (pin "2") (pinfunction "K_2") (pintype "passive"))
      (node (ref "D12") (pin "1") (pinfunction "A_1") (pintype "passive"))
      (node (ref "R16") (pin "1") (pinfunction "1_1") (pintype "passive"))
      (node (ref "U9") (pin "1") (pinfunction "Q_1") (pintype "output"))
    )
    (net (code "35") (name "Net-(D13-G)") (class "Default")
      (node (ref "D13") (pin "3") (pinfunction "G_3") (pintype "passive"))
      (node (ref "U10") (pin "6") (pinfunction "MT2_6") (pintype "passive"))
    )
    (net (code "36") (name "Net-(D14-A)") (class "Default")
      (node (ref "D14") (pin "1") (pinfunction "A_1") (pintype "passive"))
      (node (ref "R19") (pin "1") (pinfunction "1_1") (pintype "passive"))
    )
    (net (code "37") (name "Net-(D14-K)") (class "Default")
      (node (ref "D14") (pin "2") (pinfunction "K_2") (pintype "passive"))
      (node (ref "D15") (pin "1") (pinfunction "A_1") (pintype "passive"))
      (node (ref "R20") (pin "1") (pinfunction "1_1") (pintype "passive"))
      (node (ref "U11") (pin "1") (pinfunction "Q_1") (pintype "output"))
    )
    (net (code "38") (name "Net-(D16-A)") (class "Default")
      (node (ref "D16") (pin "1") (pinfunction "A_1") (pintype "passive"))
      (node (ref "R22") (pin "1") (pinfunction "1_1") (pintype "passive"))
    )
    (net (code "39") (name "Net-(D16-K)") (class "Default")
      (node (ref "D16") (pin "2") (pinfunction "K_2") (pintype "passive"))
      (node (ref "D17") (pin "1") (pinfunction "A_1") (pintype "passive"))
      (node (ref "R23") (pin "1") (pinfunction "1_1") (pintype "passive"))
      (node (ref "U12") (pin "1") (pinfunction "Q_1") (pintype "output"))
    )
    (net (code "40") (name "Net-(D18-A)") (class "Default")
      (node (ref "D18") (pin "1") (pinfunction "A_1") (pintype "passive"))
      (node (ref "R24") (pin "1") (pinfunction "1_1") (pintype "passive"))
    )
    (net (code "41") (name "Net-(D18-K)") (class "Default")
      (node (ref "D18") (pin "2") (pinfunction "K_2") (pintype "passive"))
      (node (ref "D19") (pin "1") (pinfunction "A_1") (pintype "passive"))
      (node (ref "R25") (pin "1") (pinfunction "1_1") (pintype "passive"))
      (node (ref "U13") (pin "1") (pinfunction "Q_1") (pintype "output"))
    )
    (net (code "42") (name "Net-(R20-Pad2)") (class "Default")
      (node (ref "R20") (pin "2") (pinfunction "2_2") (pintype "passive"))
      (node (ref "R21") (pin "1") (pinfunction "1_1") (pintype "passive"))
    )
    (net (code "43") (name "Net-(U1-I)") (class "Default")
      (node (ref "C1") (pin "1") (pinfunction "1_1") (pintype "passive"))
      (node (ref "C1") (pin "2") (pinfunction "2_2") (pintype "passive"))
      (node (ref "C2") (pin "1") (pinfunction "1_1") (pintype "passive"))
      (node (ref "U1") (pin "3") (pinfunction "I_3") (pintype "bidirectional"))
    )
    (net (code "44") (name "Net-(U2-MT1)") (class "Default")
      (node (ref "R3") (pin "1") (pinfunction "1_1") (pintype "passive"))
      (node (ref "U2") (pin "4") (pinfunction "MT1_4") (pintype "passive"))
    )
    (net (code "45") (name "Net-(U3-I)") (class "Default")
      (node (ref "C5") (pin "1") (pinfunction "1_1") (pintype "passive"))
      (node (ref "C5") (pin "2") (pinfunction "2_2") (pintype "passive"))
      (node (ref "C6") (pin "1") (pinfunction "1_1") (pintype "passive"))
      (node (ref "U3") (pin "3") (pinfunction "I_3") (pintype "bidirectional"))
    )
    (net (code "46") (name "Net-(U4-MT1)") (class "Default")
      (node (ref "R7") (pin "1") (pinfunction "1_1") (pintype "passive"))
      (node (ref "U4") (pin "4") (pinfunction "MT1_4") (pintype "passive"))
    )
    (net (code "47") (name "Net-(U5-2_1)") (class "Default")
      (node (ref "R9") (pin "1") (pinfunction "1_1") (pintype "passive"))
      (node (ref "U5") (pin "3") (pinfunction "2_1_3") (pintype "output"))
    )
    (net (code "48") (name "Net-(U6-I)") (class "Default")
      (node (ref "C10") (pin "1") (pinfunction "1_1") (pintype "passive"))
      (node (ref "C10") (pin "2") (pinfunction "2_2") (pintype "passive"))
      (node (ref "C11") (pin "1") (pinfunction "1_1") (pintype "passive"))
      (node (ref "U6") (pin "3") (pinfunction "I_3") (pintype "bidirectional"))
    )
    (net (code "49") (name "Net-(U7-MT1)") (class "Default")
      (node (ref "R13") (pin "1") (pinfunction "1_1") (pintype "passive"))
      (node (ref "U7") (pin "4") (pinfunction "MT1_4") (pintype "passive"))
    )
    (net (code "50") (name "Net-(U8-OUT)") (class "Default")
      (node (ref "P2") (pin "6") (pinfunction "6_6") (pintype "passive"))
      (node (ref "U8") (pin "2") (pinfunction "OUT_2") (pintype "power_in"))
      (node (ref "U8") (pin "4") (pinfunction "TAB_4") (pintype "power_in"))
    )
    (net (code "51") (name "Net-(U9-I)") (class "Default")
      (node (ref "C15") (pin "1") (pinfunction "1_1") (pintype "passive"))
      (node (ref "C15") (pin "2") (pinfunction "2_2") (pintype "passive"))
      (node (ref "C16") (pin "1") (pinfunction "1_1") (pintype "passive"))
      (node (ref "U9") (pin "3") (pinfunction "I_3") (pintype "bidirectional"))
    )
    (net (code "52") (name "Net-(U10-MT1)") (class "Default")
      (node (ref "R17") (pin "1") (pinfunction "1_1") (pintype "passive"))
      (node (ref "U10") (pin "4") (pinfunction "MT1_4") (pintype "passive"))
    )
    (net (code "53") (name "Net-(U11-I)") (class "Default")
      (node (ref "C19") (pin "1") (pinfunction "1_1") (pintype "passive"))
      (node (ref "C19") (pin "2") (pinfunction "2_2") (pintype "passive"))
      (node (ref "C20") (pin "1") (pinfunction "1_1") (pintype "passive"))
      (node (ref "U11") (pin "3") (pinfunction "I_3") (pintype "bidirectional"))
    )
    (net (code "54") (name "Net-(U12-I)") (class "Default")
      (node (ref "C22") (pin "1") (pinfunction "1_1") (pintype "passive"))
      (node (ref "C22") (pin "2") (pinfunction "2_2") (pintype "passive"))
      (node (ref "C23") (pin "1") (pinfunction "1_1") (pintype "passive"))
      (node (ref "U12") (pin "3") (pinfunction "I_3") (pintype "bidirectional"))
    )
    (net (code "55") (name "Net-(U13-I)") (class "Default")
      (node (ref "C25") (pin "1") (pinfunction "1_1") (pintype "passive"))
      (node (ref "C25") (pin "2") (pinfunction "2_2") (pintype "passive"))
      (node (ref "C26") (pin "1") (pinfunction "1_1") (pintype "passive"))
      (node (ref "U13") (pin "3") (pinfunction "I_3") (pintype "bidirectional"))
    )
    (net (code "56") (name "VCC") (class "Default")
      (node (ref "C13") (pin "2") (pinfunction "2_2") (pintype "passive"))
      (node (ref "C17") (pin "2") (pinfunction "2_2") (pintype "passive"))
      (node (ref "C21") (pin "2") (pinfunction "2_2") (pintype "passive"))
      (node (ref "C24") (pin "2") (pinfunction "2_2") (pintype "passive"))
      (node (ref "C27") (pin "2") (pinfunction "2_2") (pintype "passive"))
      (node (ref "C3") (pin "2") (pinfunction "2_2") (pintype "passive"))
      (node (ref "C7") (pin "2") (pinfunction "2_2") (pintype "passive"))
      (node (ref "C9") (pin "2") (pinfunction "+_2") (pintype "passive"))
      (node (ref "D7") (pin "2") (pinfunction "K_2") (pintype "passive"))
      (node (ref "P1") (pin "6") (pinfunction "6_6") (pintype "passive"))
      (node (ref "P3") (pin "6") (pinfunction "6_6") (pintype "passive"))
      (node (ref "R1") (pin "2") (pinfunction "2_2") (pintype "passive"))
      (node (ref "R10") (pin "2") (pinfunction "2_2") (pintype "passive"))
      (node (ref "R15") (pin "2") (pinfunction "2_2") (pintype "passive"))
      (node (ref "R19") (pin "2") (pinfunction "2_2") (pintype "passive"))
      (node (ref "R22") (pin "2") (pinfunction "2_2") (pintype "passive"))
      (node (ref "R24") (pin "2") (pinfunction "2_2") (pintype "passive"))
      (node (ref "R5") (pin "2") (pinfunction "2_2") (pintype "passive"))
      (node (ref "U1") (pin "5") (pinfunction "VDD_5") (pintype "power_in"))
      (node (ref "U1") (pin "6") (pinfunction "LPMB_6") (pintype "input"))
      (node (ref "U11") (pin "5") (pinfunction "VDD_5") (pintype "power_in"))
      (node (ref "U11") (pin "6") (pinfunction "LPMB_6") (pintype "input"))
      (node (ref "U12") (pin "5") (pinfunction "VDD_5") (pintype "power_in"))
      (node (ref "U12") (pin "6") (pinfunction "LPMB_6") (pintype "input"))
      (node (ref "U13") (pin "5") (pinfunction "VDD_5") (pintype "power_in"))
      (node (ref "U13") (pin "6") (pinfunction "LPMB_6") (pintype "input"))
      (node (ref "U3") (pin "5") (pinfunction "VDD_5") (pintype "power_in"))
      (node (ref "U3") (pin "6") (pinfunction "LPMB_6") (pintype "input"))
      (node (ref "U5") (pin "1") (pinfunction "1_1") (pintype "input"))
      (node (ref "U6") (pin "5") (pinfunction "VDD_5") (pintype "power_in"))
      (node (ref "U6") (pin "6") (pinfunction "LPMB_6") (pintype "input"))
      (node (ref "U8") (pin "3") (pinfunction "IN_3") (pintype "power_in"))
      (node (ref "U9") (pin "5") (pinfunction "VDD_5") (pintype "power_in"))
      (node (ref "U9") (pin "6") (pinfunction "LPMB_6") (pintype "input"))
    )
    (net (code "57") (name "unconnected-(P3-Pad3)") (class "Default")
      (node (ref "P3") (pin "3") (pinfunction "3_3") (pintype "passive"))
    )
    (net (code "58") (name "unconnected-(U1-VSS-Pad4)") (class "Default")
      (node (ref "U1") (pin "4") (pinfunction "VSS_4") (pintype "power_in"))
    )
    (net (code "59") (name "unconnected-(U3-VSS-Pad4)") (class "Default")
      (node (ref "U3") (pin "4") (pinfunction "VSS_4") (pintype "power_in"))
    )
    (net (code "60") (name "unconnected-(U6-VSS-Pad4)") (class "Default")
      (node (ref "U6") (pin "4") (pinfunction "VSS_4") (pintype "power_in"))
    )
    (net (code "61") (name "unconnected-(U9-VSS-Pad4)") (class "Default")
      (node (ref "U9") (pin "4") (pinfunction "VSS_4") (pintype "power_in"))
    )
    (net (code "62") (name "unconnected-(U11-VSS-Pad4)") (class "Default")
      (node (ref "U11") (pin "4") (pinfunction "VSS_4") (pintype "power_in"))
    )
    (net (code "63") (name "unconnected-(U12-VSS-Pad4)") (class "Default")
      (node (ref "U12") (pin "4") (pinfunction "VSS_4") (pintype "power_in"))
    )
    (net (code "64") (name "unconnected-(U13-VSS-Pad4)") (class "Default")
      (node (ref "U13") (pin "4") (pinfunction "VSS_4") (pintype "power_in"))
    )
  )
)
